# Power.net
KiCad netlist of a schematic drawn in Altium Designer
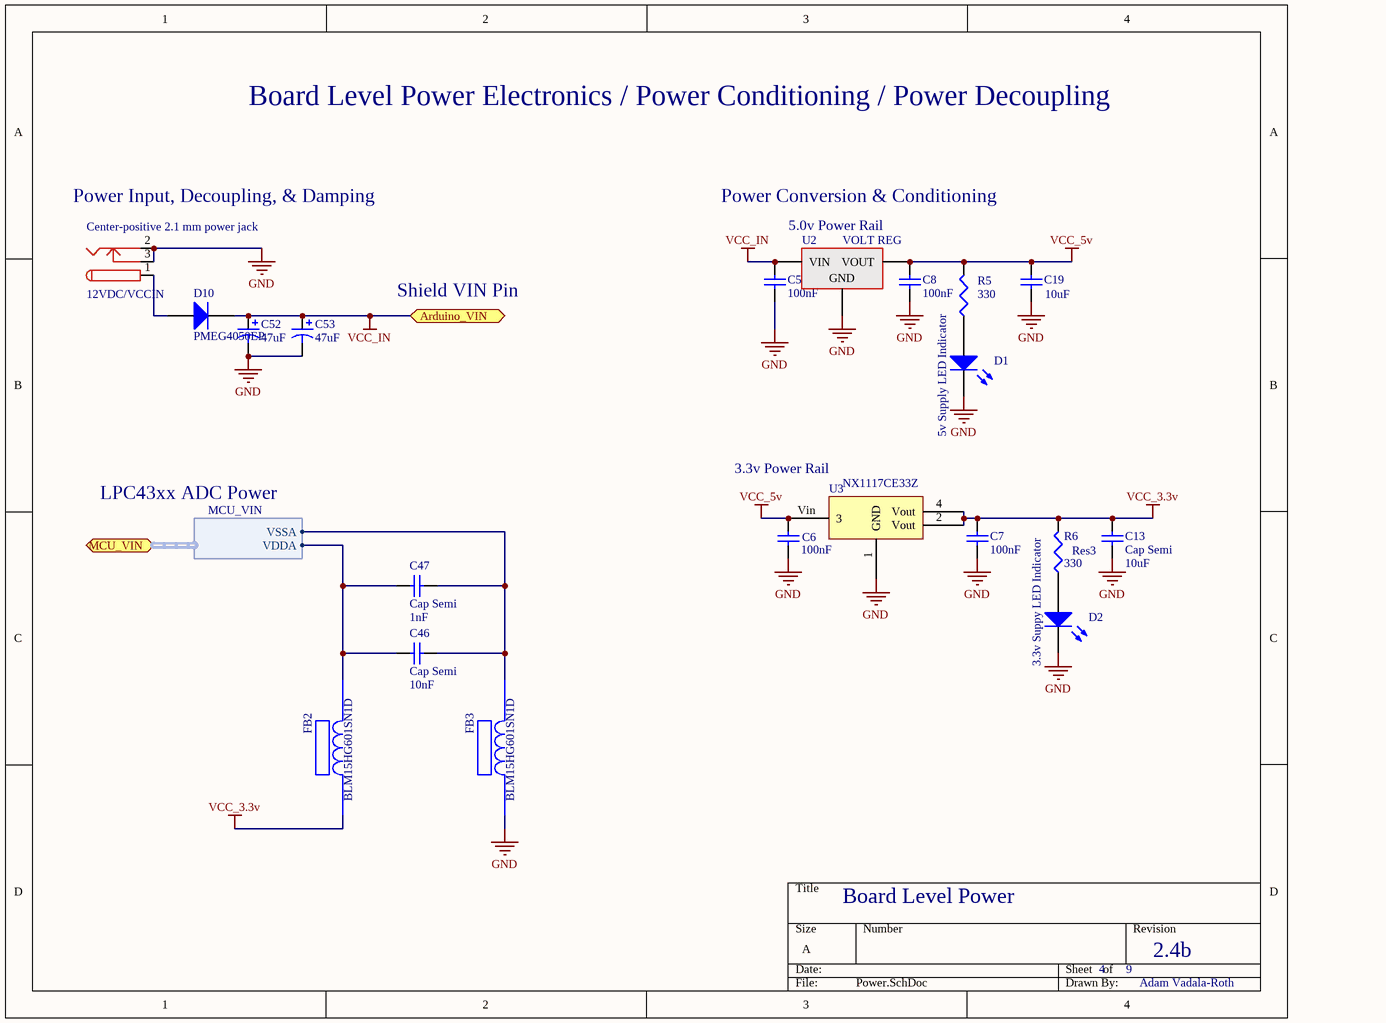
[diagram p0: Power.SchDoc]

(export (version "E")
  (design (tool "Eeschema 10.0.6"))
  (components
    (comp (ref "12VDC/VCCIN")
      (value "Center-positive 2.1 mm power jack")
      (footprint "PJ-102AH")
      (description "Power jack")
      (fields (field (name "PUBLISHER") "Altium Limited"))
      (libsource (lib "Rascal") (part "PWR2.5"))
    )
    (comp (ref "C5")
      (value "100nF")
      (footprint "C1206")
      (description "Capacitor (Semiconductor SIM Model)")
      (fields (field (name "Comment") "Cap Semi") (field (name "PUBLISHER") "Altium Limited"))
      (libsource (lib "Miscellaneous Devices") (part "Cap Semi"))
    )
    (comp (ref "C6")
      (value "100nF")
      (footprint "C1206")
      (description "Capacitor (Semiconductor SIM Model)")
      (fields (field (name "Comment") "Cap Semi") (field (name "PUBLISHER") "Altium Limited"))
      (libsource (lib "Miscellaneous Devices") (part "Cap Semi"))
    )
    (comp (ref "C7")
      (value "100nF")
      (footprint "C1206")
      (description "Capacitor (Semiconductor SIM Model)")
      (fields (field (name "Comment") "Cap Semi") (field (name "PUBLISHER") "Altium Limited"))
      (libsource (lib "Miscellaneous Devices") (part "Cap Semi"))
    )
    (comp (ref "C8")
      (value "100nF")
      (footprint "C1206")
      (description "Capacitor (Semiconductor SIM Model)")
      (fields (field (name "Comment") "Cap Semi") (field (name "PUBLISHER") "Altium Limited"))
      (libsource (lib "Miscellaneous Devices") (part "Cap Semi"))
    )
    (comp (ref "C13")
      (value "Cap Semi")
      (footprint "C1206")
      (description "Capacitor (Semiconductor SIM Model)")
      (fields (field (name "ALTIUM_VALUE") "10uF") (field (name "PUBLISHER") "Altium Limited"))
      (libsource (lib "Miscellaneous Devices") (part "Cap Semi"))
    )
    (comp (ref "C19")
      (value "10uF")
      (footprint "C1206")
      (description "Capacitor (Semiconductor SIM Model)")
      (fields (field (name "Comment") "Cap Semi") (field (name "PUBLISHER") "Altium Limited"))
      (libsource (lib "Miscellaneous Devices") (part "Cap Semi"))
    )
    (comp (ref "C46")
      (value "Cap Semi")
      (footprint "1608[0603]")
      (description "Capacitor (Semiconductor SIM Model)")
      (fields (field (name "ALTIUM_VALUE") "10nF") (field (name "PUBLISHER") "Altium Limited"))
      (libsource (lib "Miscellaneous Devices") (part "Cap Semi"))
    )
    (comp (ref "C47")
      (value "Cap Semi")
      (footprint "1608[0603]")
      (description "Capacitor (Semiconductor SIM Model)")
      (fields (field (name "ALTIUM_VALUE") "1nF") (field (name "PUBLISHER") "Altium Limited"))
      (libsource (lib "Miscellaneous Devices") (part "Cap Semi"))
    )
    (comp (ref "C52")
      (value "47uF")
      (footprint "CAPPR2.5-6.3x5")
      (description "Polarized Capacitor (Radial)")
      (fields (field (name "Comment") "Cap Pol1") (field (name "PUBLISHER") "Altium Limited"))
      (libsource (lib "Miscellaneous Devices") (part "Cap Pol1"))
    )
    (comp (ref "C53")
      (value "47uF")
      (footprint "CAPPR2.5-6.3x5")
      (description "Polarized Capacitor (Radial)")
      (fields (field (name "Comment") "Cap Pol1") (field (name "PUBLISHER") "Altium Limited"))
      (libsource (lib "Miscellaneous Devices") (part "Cap Pol1"))
    )
    (comp (ref "D1")
      (value "LED2")
      (footprint "3.2X1.6X1.1")
      (description "Typical RED, GREEN, YELLOW, AMBER GaAs LED")
      (fields (field (name "PUBLISHER") "Altium Limited"))
      (libsource (lib "Miscellaneous Devices") (part "LED2"))
    )
    (comp (ref "D2")
      (value "LED2")
      (footprint "3.2X1.6X1.1")
      (description "Typical RED, GREEN, YELLOW, AMBER GaAs LED")
      (fields (field (name "PUBLISHER") "Altium Limited"))
      (libsource (lib "Miscellaneous Devices") (part "LED2"))
    )
    (comp (ref "D10")
      (value "PMEG4050EP")
      (footprint "PMEG4050EP")
      (description "Default Diode")
      (fields (field (name "PUBLISHER") "Altium Limited"))
      (libsource (lib "Miscellaneous Devices") (part "Diode"))
    )
    (comp (ref "FB2")
      (value "BLM15HG601SN1D")
      (footprint "BLM18PG121SN1D")
      (libsource (lib "AHD Part Library") (part "BLM15HG601SN1D"))
    )
    (comp (ref "FB3")
      (value "BLM15HG601SN1D")
      (footprint "BLM18PG121SN1D")
      (libsource (lib "AHD Part Library") (part "BLM15HG601SN1D"))
    )
    (comp (ref "R5")
      (value "330")
      (footprint "0805 SMD Resistor")
      (description "Resistor")
      (fields (field (name "Comment") "Res3") (field (name "PUBLISHER") "Altium Limited"))
      (libsource (lib "Miscellaneous Devices") (part "Res3"))
    )
    (comp (ref "R6")
      (value "Res3")
      (footprint "0805 SMD Resistor")
      (description "Resistor")
      (fields (field (name "ALTIUM_VALUE") "330") (field (name "PUBLISHER") "Altium Limited"))
      (libsource (lib "Miscellaneous Devices") (part "Res3"))
    )
    (comp (ref "U2")
      (value "VOLT REG")
      (footprint "DPAK-3")
      (description "Voltage regulator")
      (fields (field (name "PUBLISHER") "Altium Limited"))
      (libsource (lib "Rascal") (part "VOLT REG"))
    )
    (comp (ref "U3")
      (value "NX1117CE33Z")
      (footprint "NX1117CE33Z")
      (description "3.3v Linear Regulator")
      (libsource (lib "AHD Part Library") (part "NX1117CE33Z"))
    )
  )
  (nets
    (net (code "3") (name "GND") (class "Default")
      (node (ref "12VDC/VCCIN") (pin "2") (pinfunction "2_2") (pintype "power_in"))
      (node (ref "12VDC/VCCIN") (pin "3") (pinfunction "3_3") (pintype "power_in"))
      (node (ref "C13") (pin "1") (pinfunction "1_1") (pintype "passive"))
      (node (ref "C19") (pin "1") (pinfunction "1_1") (pintype "passive"))
      (node (ref "C5") (pin "1") (pinfunction "1_1") (pintype "passive"))
      (node (ref "C52") (pin "2") (pinfunction "2_2") (pintype "passive"))
      (node (ref "C53") (pin "2") (pinfunction "2_2") (pintype "passive"))
      (node (ref "C6") (pin "1") (pinfunction "1_1") (pintype "passive"))
      (node (ref "C7") (pin "1") (pinfunction "1_1") (pintype "passive"))
      (node (ref "C8") (pin "1") (pinfunction "1_1") (pintype "passive"))
      (node (ref "D1") (pin "2") (pinfunction "K_2") (pintype "passive"))
      (node (ref "D2") (pin "2") (pinfunction "K_2") (pintype "passive"))
      (node (ref "FB3") (pin "1") (pinfunction "1_1") (pintype "passive"))
      (node (ref "U2") (pin "2") (pinfunction "GND_2") (pintype "passive"))
      (node (ref "U3") (pin "1") (pinfunction "GND_1") (pintype "passive"))
    )
    (net (code "4") (name "Net-(C46-Pad1)") (class "Default")
      (node (ref "C46") (pin "1") (pinfunction "1_1") (pintype "passive"))
      (node (ref "C47") (pin "1") (pinfunction "1_1") (pintype "passive"))
      (node (ref "FB2") (pin "2") (pinfunction "2_2") (pintype "passive"))
    )
    (net (code "5") (name "Net-(C46-Pad2)") (class "Default")
      (node (ref "C46") (pin "2") (pinfunction "2_2") (pintype "passive"))
      (node (ref "C47") (pin "2") (pinfunction "2_2") (pintype "passive"))
      (node (ref "FB3") (pin "2") (pinfunction "2_2") (pintype "passive"))
    )
    (net (code "6") (name "Net-(D1-A)") (class "Default")
      (node (ref "D1") (pin "1") (pinfunction "A_1") (pintype "passive"))
      (node (ref "R5") (pin "1") (pinfunction "1_1") (pintype "passive"))
    )
    (net (code "7") (name "Net-(D2-A)") (class "Default")
      (node (ref "D2") (pin "1") (pinfunction "A_1") (pintype "passive"))
      (node (ref "R6") (pin "1") (pinfunction "1_1") (pintype "passive"))
    )
    (net (code "8") (name "Net-(D10-A)") (class "Default")
      (node (ref "12VDC/VCCIN") (pin "1") (pinfunction "1_1") (pintype "power_in"))
      (node (ref "D10") (pin "1") (pinfunction "A_1") (pintype "passive"))
    )
    (net (code "9") (name "VCC_3.3v") (class "Default")
      (node (ref "C13") (pin "2") (pinfunction "2_2") (pintype "passive"))
      (node (ref "C7") (pin "2") (pinfunction "2_2") (pintype "passive"))
      (node (ref "FB2") (pin "1") (pinfunction "1_1") (pintype "passive"))
      (node (ref "R6") (pin "2") (pinfunction "2_2") (pintype "passive"))
      (node (ref "U3") (pin "2") (pinfunction "Vout_2") (pintype "passive"))
      (node (ref "U3") (pin "4") (pinfunction "Vout_4") (pintype "passive"))
    )
    (net (code "10") (name "VCC_5v") (class "Default")
      (node (ref "C19") (pin "2") (pinfunction "2_2") (pintype "passive"))
      (node (ref "C6") (pin "2") (pinfunction "2_2") (pintype "passive"))
      (node (ref "C8") (pin "2") (pinfunction "2_2") (pintype "passive"))
      (node (ref "R5") (pin "2") (pinfunction "2_2") (pintype "passive"))
      (node (ref "U2") (pin "3") (pinfunction "VOUT_3") (pintype "passive"))
      (node (ref "U3") (pin "Vin") (pinfunction "3_Vin") (pintype "passive"))
    )
    (net (code "11") (name "VCC_IN") (class "Default")
      (node (ref "C5") (pin "2") (pinfunction "2_2") (pintype "passive"))
      (node (ref "C52") (pin "1") (pinfunction "1_1") (pintype "passive"))
      (node (ref "C53") (pin "1") (pinfunction "1_1") (pintype "passive"))
      (node (ref "D10") (pin "2") (pinfunction "K_2") (pintype "passive"))
      (node (ref "U2") (pin "1") (pinfunction "VIN_1") (pintype "passive"))
    )
  )
)
